# SysACE_SysFLASH.net
KiCad netlist of a schematic drawn in Altium Designer
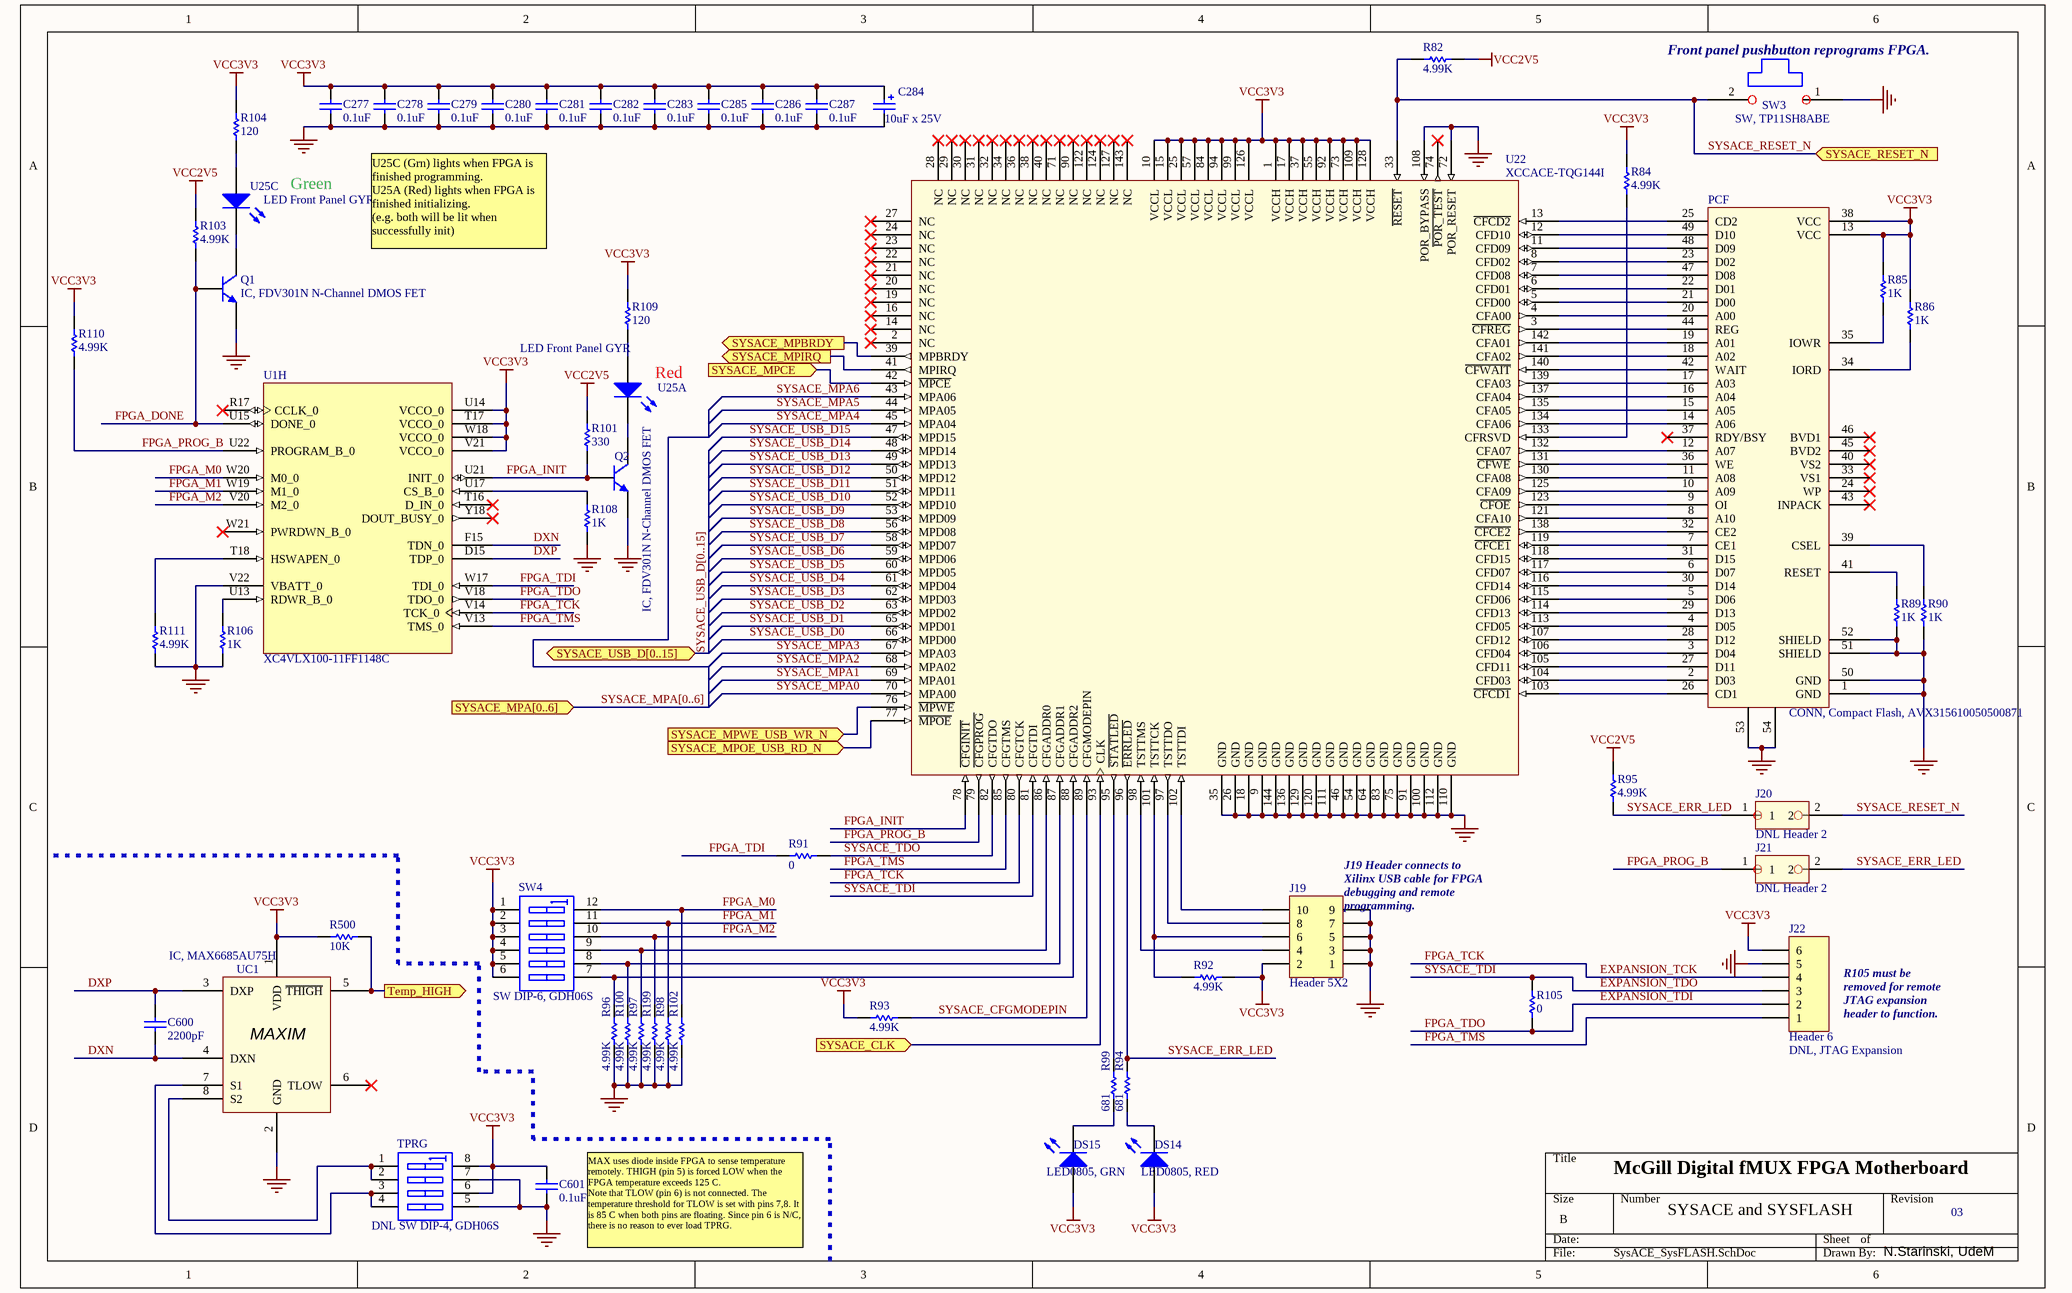
[diagram p0: SysACE_SysFLASH.SchDoc]

(export (version "E")
  (design (tool "Eeschema 10.0.6"))
  (components
    (comp (ref "C277")
      (value "0.1uF")
      (footprint "CC1608-0603")
      (description "Capacitor (Semiconductor SIM Model)")
      (fields (field (name "PUBLISHER") "Altium Limited"))
      (libsource (lib "Miscellaneous Devices") (part "Cap Semi"))
    )
    (comp (ref "C278")
      (value "0.1uF")
      (footprint "CC1608-0603")
      (description "Capacitor (Semiconductor SIM Model)")
      (fields (field (name "PUBLISHER") "Altium Limited"))
      (libsource (lib "Miscellaneous Devices") (part "Cap Semi"))
    )
    (comp (ref "C279")
      (value "0.1uF")
      (footprint "CC1608-0603")
      (description "Capacitor (Semiconductor SIM Model)")
      (fields (field (name "PUBLISHER") "Altium Limited"))
      (libsource (lib "Miscellaneous Devices") (part "Cap Semi"))
    )
    (comp (ref "C280")
      (value "0.1uF")
      (footprint "CC1608-0603")
      (description "Capacitor (Semiconductor SIM Model)")
      (fields (field (name "PUBLISHER") "Altium Limited"))
      (libsource (lib "Miscellaneous Devices") (part "Cap Semi"))
    )
    (comp (ref "C281")
      (value "0.1uF")
      (footprint "CC1608-0603")
      (description "Capacitor (Semiconductor SIM Model)")
      (fields (field (name "PUBLISHER") "Altium Limited"))
      (libsource (lib "Miscellaneous Devices") (part "Cap Semi"))
    )
    (comp (ref "C282")
      (value "0.1uF")
      (footprint "CC1608-0603")
      (description "Capacitor (Semiconductor SIM Model)")
      (fields (field (name "PUBLISHER") "Altium Limited"))
      (libsource (lib "Miscellaneous Devices") (part "Cap Semi"))
    )
    (comp (ref "C283")
      (value "0.1uF")
      (footprint "CC1608-0603")
      (description "Capacitor (Semiconductor SIM Model)")
      (fields (field (name "PUBLISHER") "Altium Limited"))
      (libsource (lib "Miscellaneous Devices") (part "Cap Semi"))
    )
    (comp (ref "C284")
      (value "10uF x 25V")
      (footprint "TC6032-2412")
      (description "CAP POL B45197A5106K309")
      (fields (field (name "PUBLISHER") "Altium Limited"))
      (libsource (lib "Miscellaneous Devices 02") (part "Cap Pol3"))
    )
    (comp (ref "C285")
      (value "0.1uF")
      (footprint "CC1608-0603")
      (description "Capacitor (Semiconductor SIM Model)")
      (fields (field (name "PUBLISHER") "Altium Limited"))
      (libsource (lib "Miscellaneous Devices") (part "Cap Semi"))
    )
    (comp (ref "C286")
      (value "0.1uF")
      (footprint "CC1608-0603")
      (description "Capacitor (Semiconductor SIM Model)")
      (fields (field (name "PUBLISHER") "Altium Limited"))
      (libsource (lib "Miscellaneous Devices") (part "Cap Semi"))
    )
    (comp (ref "C287")
      (value "0.1uF")
      (footprint "CC1608-0603")
      (description "Capacitor (Semiconductor SIM Model)")
      (fields (field (name "PUBLISHER") "Altium Limited"))
      (libsource (lib "Miscellaneous Devices") (part "Cap Semi"))
    )
    (comp (ref "C600")
      (value "2200pF")
      (footprint "CC1608-0603")
      (description "Capacitor (Semiconductor SIM Model)")
      (fields (field (name "PUBLISHER") "Altium Limited"))
      (libsource (lib "Miscellaneous Devices") (part "Cap Semi"))
    )
    (comp (ref "C601")
      (value "0.1uF")
      (footprint "CC1608-0603")
      (description "Capacitor (Semiconductor SIM Model)")
      (fields (field (name "PUBLISHER") "Altium Limited"))
      (libsource (lib "Miscellaneous Devices") (part "Cap Semi"))
    )
    (comp (ref "DS14")
      (value "LED0805, RED")
      (footprint "SMD _LED")
      (description "LED 0805 LTST-C170CKT")
      (fields (field (name "PUBLISHER") "Altium Limited"))
      (libsource (lib "Miscellaneous Devices") (part "LED3"))
    )
    (comp (ref "DS15")
      (value "LED0805, GRN")
      (footprint "SMD _LED")
      (description "LED 0805 LTST-C170GKT")
      (fields (field (name "PUBLISHER") "Altium Limited"))
      (libsource (lib "Miscellaneous Devices") (part "LED3"))
    )
    (comp (ref "J19")
      (value "Header 5X2")
      (footprint "HDR2X5")
      (description "Header, 0.1\" 5-Pin, Dual row straight")
      (fields (field (name "PUBLISHER") "Altium Limited"))
      (libsource (lib "Miscellaneous Connectors") (part "Header 5X2"))
    )
    (comp (ref "J20")
      (value "DNL Header 2")
      (footprint "HDR1X2")
      (description "Header, 0.1\" 2-Pin straight")
      (libsource (lib "MyComp1") (part "Jumper_100mil"))
    )
    (comp (ref "J21")
      (value "DNL Header 2")
      (footprint "HDR1X2")
      (description "Header, 0.1\" 2-Pin straight")
      (libsource (lib "MyComp1") (part "Jumper_100mil"))
    )
    (comp (ref "J22")
      (value "Header 6")
      (footprint "HDR1X6")
      (description "Header, 0.1\" 6-Pin straight")
      (fields (field (name "ASSEMBLY") "DNL, JTAG Expansion") (field (name "PUBLISHER") "Altium Limited"))
      (libsource (lib "Miscellaneous Connectors") (part "Header 6"))
    )
    (comp (ref "PCF")
      (value "CONN, Compact Flash, AVX315610050500871")
      (footprint "CF_AVX5611")
      (description "Compact Flash Connector")
      (libsource (lib "MyComp1") (part "CF_Conn"))
    )
    (comp (ref "Q1")
      (value "IC, FDV301N N-Channel DMOS FET")
      (footprint "Philips Discrete BJT - Low Power:SOT23")
      (description "NPN Switching Transistor")
      (fields (field (name "PUBLISHER") "Altium Limited"))
      (libsource (lib "Philips Discrete BJT - Low Power") (part "MMBT3904"))
    )
    (comp (ref "Q2")
      (value "IC, FDV301N N-Channel DMOS FET")
      (footprint "Philips Discrete BJT - Low Power:SOT23")
      (description "NPN Switching Transistor")
      (fields (field (name "PUBLISHER") "Altium Limited"))
      (libsource (lib "Philips Discrete BJT - Low Power") (part "MMBT3904"))
    )
    (comp (ref "R82")
      (value "4.99K")
      (footprint "CR1608-0603")
      (description "Resistor 0603")
      (fields (field (name "PUBLISHER") "Altium Limited"))
      (libsource (lib "Miscellaneous Devices") (part "Res Semi"))
    )
    (comp (ref "R84")
      (value "4.99K")
      (footprint "CR1608-0603")
      (description "Resistor 0603")
      (fields (field (name "PUBLISHER") "Altium Limited"))
      (libsource (lib "Miscellaneous Devices") (part "Res Semi"))
    )
    (comp (ref "R85")
      (value "1K")
      (footprint "CR1608-0603")
      (description "Resistor 0603")
      (fields (field (name "PUBLISHER") "Altium Limited"))
      (libsource (lib "Miscellaneous Devices") (part "Res Semi"))
    )
    (comp (ref "R86")
      (value "1K")
      (footprint "CR1608-0603")
      (description "Resistor 0603")
      (fields (field (name "PUBLISHER") "Altium Limited"))
      (libsource (lib "Miscellaneous Devices") (part "Res Semi"))
    )
    (comp (ref "R89")
      (value "1K")
      (footprint "CR1608-0603")
      (description "Resistor 0603")
      (fields (field (name "PUBLISHER") "Altium Limited"))
      (libsource (lib "Miscellaneous Devices") (part "Res Semi"))
    )
    (comp (ref "R90")
      (value "1K")
      (footprint "CR1608-0603")
      (description "Resistor 0603")
      (fields (field (name "PUBLISHER") "Altium Limited"))
      (libsource (lib "Miscellaneous Devices") (part "Res Semi"))
    )
    (comp (ref "R91")
      (value "0")
      (footprint "CR1608-0603")
      (description "Resistor 0603")
      (fields (field (name "PUBLISHER") "Altium Limited"))
      (libsource (lib "Miscellaneous Devices") (part "Res Semi"))
    )
    (comp (ref "R92")
      (value "4.99K")
      (footprint "CR1608-0603")
      (description "Resistor 0603")
      (fields (field (name "PUBLISHER") "Altium Limited"))
      (libsource (lib "Miscellaneous Devices") (part "Res Semi"))
    )
    (comp (ref "R93")
      (value "4.99K")
      (footprint "CR1608-0603")
      (description "Resistor 0603")
      (fields (field (name "PUBLISHER") "Altium Limited"))
      (libsource (lib "Miscellaneous Devices") (part "Res Semi"))
    )
    (comp (ref "R94")
      (value "681")
      (footprint "CR1608-0603")
      (description "Resistor 0603")
      (fields (field (name "PUBLISHER") "Altium Limited"))
      (libsource (lib "Miscellaneous Devices") (part "Res Semi"))
    )
    (comp (ref "R95")
      (value "4.99K")
      (footprint "CR1608-0603")
      (description "Resistor 0603")
      (fields (field (name "PUBLISHER") "Altium Limited"))
      (libsource (lib "Miscellaneous Devices") (part "Res Semi"))
    )
    (comp (ref "R96")
      (value "4.99K")
      (footprint "CR1608-0603")
      (description "Resistor 0603")
      (fields (field (name "PUBLISHER") "Altium Limited"))
      (libsource (lib "Miscellaneous Devices") (part "Res Semi"))
    )
    (comp (ref "R97")
      (value "4.99K")
      (footprint "CR1608-0603")
      (description "Resistor 0603")
      (fields (field (name "PUBLISHER") "Altium Limited"))
      (libsource (lib "Miscellaneous Devices") (part "Res Semi"))
    )
    (comp (ref "R98")
      (value "4.99K")
      (footprint "CR1608-0603")
      (description "Resistor 0603")
      (fields (field (name "PUBLISHER") "Altium Limited"))
      (libsource (lib "Miscellaneous Devices") (part "Res Semi"))
    )
    (comp (ref "R99")
      (value "681")
      (footprint "CR1608-0603")
      (description "Resistor 0603")
      (fields (field (name "PUBLISHER") "Altium Limited"))
      (libsource (lib "Miscellaneous Devices") (part "Res Semi"))
    )
    (comp (ref "R100")
      (value "4.99K")
      (footprint "CR1608-0603")
      (description "Resistor 0603")
      (fields (field (name "PUBLISHER") "Altium Limited"))
      (libsource (lib "Miscellaneous Devices") (part "Res Semi"))
    )
    (comp (ref "R101")
      (value "330")
      (footprint "CR1608-0603")
      (description "Resistor 0603")
      (fields (field (name "PUBLISHER") "Altium Limited"))
      (libsource (lib "Miscellaneous Devices") (part "Res Semi"))
    )
    (comp (ref "R102")
      (value "4.99K")
      (footprint "CR1608-0603")
      (description "Resistor 0603")
      (fields (field (name "PUBLISHER") "Altium Limited"))
      (libsource (lib "Miscellaneous Devices") (part "Res Semi"))
    )
    (comp (ref "R103")
      (value "4.99K")
      (footprint "CR1608-0603")
      (description "Resistor 0603")
      (fields (field (name "PUBLISHER") "Altium Limited"))
      (libsource (lib "Miscellaneous Devices") (part "Res Semi"))
    )
    (comp (ref "R104")
      (value "120")
      (footprint "CR1608-0603")
      (description "Resistor 0603")
      (fields (field (name "PUBLISHER") "Altium Limited"))
      (libsource (lib "Miscellaneous Devices") (part "Res Semi"))
    )
    (comp (ref "R105")
      (value "0")
      (footprint "CR1608-0603")
      (description "Resistor 0603")
      (fields (field (name "PUBLISHER") "Altium Limited"))
      (libsource (lib "Miscellaneous Devices") (part "Res Semi"))
    )
    (comp (ref "R106")
      (value "1K")
      (footprint "CR1608-0603")
      (description "Resistor 0603")
      (fields (field (name "PUBLISHER") "Altium Limited"))
      (libsource (lib "Miscellaneous Devices") (part "Res Semi"))
    )
    (comp (ref "R108")
      (value "1K")
      (footprint "CR1608-0603")
      (description "Resistor 0603")
      (fields (field (name "PUBLISHER") "Altium Limited"))
      (libsource (lib "Miscellaneous Devices") (part "Res Semi"))
    )
    (comp (ref "R109")
      (value "120")
      (footprint "CR1608-0603")
      (description "Resistor 0603")
      (fields (field (name "PUBLISHER") "Altium Limited"))
      (libsource (lib "Miscellaneous Devices") (part "Res Semi"))
    )
    (comp (ref "R110")
      (value "4.99K")
      (footprint "CR1608-0603")
      (description "Resistor 0603")
      (fields (field (name "PUBLISHER") "Altium Limited"))
      (libsource (lib "Miscellaneous Devices") (part "Res Semi"))
    )
    (comp (ref "R111")
      (value "4.99K")
      (footprint "CR1608-0603")
      (description "Resistor 0603")
      (fields (field (name "PUBLISHER") "Altium Limited"))
      (libsource (lib "Miscellaneous Devices") (part "Res Semi"))
    )
    (comp (ref "R199")
      (value "4.99K")
      (footprint "CR1608-0603")
      (description "Resistor 0603")
      (fields (field (name "PUBLISHER") "Altium Limited"))
      (libsource (lib "Miscellaneous Devices") (part "Res Semi"))
    )
    (comp (ref "R500")
      (value "10K")
      (footprint "CR1608-0603")
      (description "Resistor 0603")
      (fields (field (name "PUBLISHER") "Altium Limited"))
      (libsource (lib "Miscellaneous Devices") (part "Res Semi"))
    )
    (comp (ref "SW3")
      (value "SW, TP11SH8ABE")
      (footprint "TP11SH8ABE")
      (description "Right angle PC trough")
      (libsource (lib "Miscellaneous Devices 02") (part "Tiny Pushbutton Switch"))
    )
    (comp (ref "SW4")
      (value "SW DIP-6, GDH06S")
      (footprint "DIP_SW_SM6POS")
      (description "DIP Switch, 6 Position, SPST")
      (fields (field (name "PUBLISHER") "Altium Limited"))
      (libsource (lib "Miscellaneous Devices 02") (part "SW DIP-6"))
    )
    (comp (ref "TPRG")
      (value "DNL SW DIP-4, GDH06S")
      (footprint "SO-G8")
      (description "DIP Switch, 4 Position, SPST")
      (fields (field (name "PUBLISHER") "Altium Limited"))
      (libsource (lib "Miscellaneous Devices 02") (part "SW DIP-4"))
    )
    (comp (ref "U1")
      (value "XC4VLX100-11FF1148C")
      (footprint "FF1148")
      (description "Xilinx Virtex-4 LX Platform FPGA, 1148-Ball FFBGA, Speed Grade 11, 768 User I/Os, Commercial Grade")
      (fields (field (name "PUBLISHER") "Altium Limited"))
      (libsource (lib "Xilinx Virtex-4") (part "XC4VLX100-11FF1148C"))
    )
    (comp (ref "U22")
      (value "XCCACE-TQG144I")
      (footprint "TQFP144")
      (description "System ACE CF Xilinx")
      (libsource (lib "Xilinx_Extra_01") (part "XCCACE-TQG144I"))
    )
    (comp (ref "U25")
      (value "LED Front Panel GYR")
      (footprint "LED_Tri_")
      (description "564-0200-132F")
      (libsource (lib "Miscellaneous Devices") (part "LED_Tri"))
    )
    (comp (ref "UC1")
      (value "IC, MAX6685AU75H")
      (footprint "uSOP8")
      (description "Dual-Output Remote-Junction Temperature Switch")
      (libsource (lib "Maxim Power Mgt Supervisory Circuit") (part "MAX6685"))
    )
  )
  (nets
    (net (code "1") (name "/DXN") (class "Default")
      (node (ref "C600") (pin "1") (pinfunction "1_1") (pintype "passive"))
      (node (ref "U1") (pin "F15") (pinfunction "TDN_0_F15") (pintype "passive"))
      (node (ref "UC1") (pin "4") (pinfunction "DXN_4") (pintype "passive"))
    )
    (net (code "2") (name "/DXP") (class "Default")
      (node (ref "C600") (pin "2") (pinfunction "2_2") (pintype "passive"))
      (node (ref "U1") (pin "D15") (pinfunction "TDP_0_D15") (pintype "passive"))
      (node (ref "UC1") (pin "3") (pinfunction "DXP_3") (pintype "passive"))
    )
    (net (code "3") (name "/EXPANSION_TCK") (class "Default")
      (node (ref "J22") (pin "4") (pinfunction "4_4") (pintype "passive"))
      (node (ref "U1") (pin "V14") (pinfunction "TCK_0_V14") (pintype "input"))
      (node (ref "U22") (pin "80") (pinfunction "CFGTCK_80") (pintype "output"))
    )
    (net (code "4") (name "/EXPANSION_TDI") (class "Default")
      (node (ref "J22") (pin "2") (pinfunction "2_2") (pintype "passive"))
      (node (ref "R105") (pin "1") (pinfunction "1_1") (pintype "passive"))
      (node (ref "U1") (pin "V18") (pinfunction "TDO_0_V18") (pintype "output"))
    )
    (net (code "5") (name "/EXPANSION_TDO") (class "Default")
      (node (ref "J22") (pin "3") (pinfunction "3_3") (pintype "passive"))
      (node (ref "R105") (pin "2") (pinfunction "2_2") (pintype "passive"))
      (node (ref "U22") (pin "81") (pinfunction "CFGTDI_81") (pintype "input"))
    )
    (net (code "6") (name "/FPGA_DONE") (class "Default")
      (node (ref "Q1") (pin "1") (pinfunction "B_1") (pintype "passive"))
      (node (ref "R103") (pin "1") (pinfunction "1_1") (pintype "passive"))
      (node (ref "U1") (pin "U15") (pinfunction "DONE_0_U15") (pintype "bidirectional"))
    )
    (net (code "7") (name "/FPGA_INIT") (class "Default")
      (node (ref "Q2") (pin "1") (pinfunction "B_1") (pintype "passive"))
      (node (ref "R101") (pin "1") (pinfunction "1_1") (pintype "passive"))
      (node (ref "U1") (pin "U21") (pinfunction "INIT_0_U21") (pintype "bidirectional"))
      (node (ref "U22") (pin "78") (pinfunction "~{CFGINIT}_78") (pintype "input"))
    )
    (net (code "8") (name "/FPGA_M0") (class "Default")
      (node (ref "R102") (pin "2") (pinfunction "2_2") (pintype "passive"))
      (node (ref "SW4") (pin "12") (pinfunction "B1_12") (pintype "passive"))
      (node (ref "U1") (pin "W20") (pinfunction "M0_0_W20") (pintype "input"))
    )
    (net (code "9") (name "/FPGA_M1") (class "Default")
      (node (ref "R98") (pin "2") (pinfunction "2_2") (pintype "passive"))
      (node (ref "SW4") (pin "11") (pinfunction "B2_11") (pintype "passive"))
      (node (ref "U1") (pin "W19") (pinfunction "M1_0_W19") (pintype "input"))
    )
    (net (code "10") (name "/FPGA_M2") (class "Default")
      (node (ref "R199") (pin "2") (pinfunction "2_2") (pintype "passive"))
      (node (ref "SW4") (pin "10") (pinfunction "B3_10") (pintype "passive"))
      (node (ref "U1") (pin "V20") (pinfunction "M2_0_V20") (pintype "input"))
    )
    (net (code "11") (name "/FPGA_PROG_B") (class "Default")
      (node (ref "J21") (pin "1") (pinfunction "1_1") (pintype "passive"))
      (node (ref "R110") (pin "1") (pinfunction "1_1") (pintype "passive"))
      (node (ref "U1") (pin "U22") (pinfunction "PROGRAM_B_0_U22") (pintype "input"))
      (node (ref "U22") (pin "79") (pinfunction "~{CFGPROG}_79") (pintype "output"))
    )
    (net (code "12") (name "/FPGA_TDI") (class "Default")
      (node (ref "R91") (pin "1") (pinfunction "1_1") (pintype "passive"))
      (node (ref "U1") (pin "W17") (pinfunction "TDI_0_W17") (pintype "input"))
    )
    (net (code "13") (name "/FPGA_TMS") (class "Default")
      (node (ref "J22") (pin "1") (pinfunction "1_1") (pintype "passive"))
      (node (ref "U1") (pin "V13") (pinfunction "TMS_0_V13") (pintype "input"))
      (node (ref "U22") (pin "85") (pinfunction "CFGTMS_85") (pintype "output"))
    )
    (net (code "14") (name "/SYSACE_CFGMODEPIN") (class "Default")
      (node (ref "R93") (pin "2") (pinfunction "2_2") (pintype "passive"))
      (node (ref "U22") (pin "89") (pinfunction "CFGMODEPIN_89") (pintype "input"))
    )
    (net (code "15") (name "/SYSACE_CLK") (class "Default")
      (node (ref "U22") (pin "93") (pinfunction "CLK_93") (pintype "input"))
    )
    (net (code "16") (name "/SYSACE_ERR_LED") (class "Default")
      (node (ref "J20") (pin "1") (pinfunction "1_1") (pintype "passive"))
      (node (ref "J21") (pin "2") (pinfunction "2_2") (pintype "passive"))
      (node (ref "R94") (pin "2") (pinfunction "2_2") (pintype "passive"))
      (node (ref "R95") (pin "1") (pinfunction "1_1") (pintype "passive"))
      (node (ref "U22") (pin "96") (pinfunction "~{ERRLED}_96") (pintype "output"))
    )
    (net (code "17") (name "/SYSACE_MPA0") (class "Default")
      (node (ref "U22") (pin "70") (pinfunction "MPA00_70") (pintype "input"))
    )
    (net (code "18") (name "/SYSACE_MPA1") (class "Default")
      (node (ref "U22") (pin "69") (pinfunction "MPA01_69") (pintype "input"))
    )
    (net (code "19") (name "/SYSACE_MPA2") (class "Default")
      (node (ref "U22") (pin "68") (pinfunction "MPA02_68") (pintype "input"))
    )
    (net (code "20") (name "/SYSACE_MPA3") (class "Default")
      (node (ref "U22") (pin "67") (pinfunction "MPA03_67") (pintype "input"))
    )
    (net (code "21") (name "/SYSACE_MPA4") (class "Default")
      (node (ref "U22") (pin "45") (pinfunction "MPA04_45") (pintype "input"))
    )
    (net (code "22") (name "/SYSACE_MPA5") (class "Default")
      (node (ref "U22") (pin "44") (pinfunction "MPA05_44") (pintype "input"))
    )
    (net (code "23") (name "/SYSACE_MPA6") (class "Default")
      (node (ref "U22") (pin "43") (pinfunction "MPA06_43") (pintype "input"))
    )
    (net (code "25") (name "/SYSACE_MPBRDY") (class "Default")
      (node (ref "U22") (pin "39") (pinfunction "MPBRDY_39") (pintype "output"))
    )
    (net (code "26") (name "/SYSACE_MPCE") (class "Default")
      (node (ref "U22") (pin "42") (pinfunction "~{MPCE}_42") (pintype "input"))
    )
    (net (code "27") (name "/SYSACE_MPIRQ") (class "Default")
      (node (ref "U22") (pin "41") (pinfunction "MPIRQ_41") (pintype "output"))
    )
    (net (code "28") (name "/SYSACE_MPOE_USB_RD_N") (class "Default")
      (node (ref "U22") (pin "77") (pinfunction "~{MPOE}_77") (pintype "input"))
    )
    (net (code "29") (name "/SYSACE_MPWE_USB_WR_N") (class "Default")
      (node (ref "U22") (pin "76") (pinfunction "~{MPWE}_76") (pintype "input"))
    )
    (net (code "30") (name "/SYSACE_RESET_N") (class "Default")
      (node (ref "J20") (pin "2") (pinfunction "2_2") (pintype "passive"))
      (node (ref "R82") (pin "1") (pinfunction "1_1") (pintype "passive"))
      (node (ref "SW3") (pin "2") (pinfunction "2_2") (pintype "passive"))
      (node (ref "U22") (pin "33") (pinfunction "~{RESET}_33") (pintype "input"))
    )
    (net (code "31") (name "/SYSACE_TDO") (class "Default")
      (node (ref "R91") (pin "2") (pinfunction "2_2") (pintype "passive"))
      (node (ref "U22") (pin "82") (pinfunction "CFGTDO_82") (pintype "output"))
    )
    (net (code "32") (name "/SYSACE_USB_D0") (class "Default")
      (node (ref "U22") (pin "66") (pinfunction "MPD00_66") (pintype "bidirectional"))
    )
    (net (code "33") (name "/SYSACE_USB_D1") (class "Default")
      (node (ref "U22") (pin "65") (pinfunction "MPD01_65") (pintype "bidirectional"))
    )
    (net (code "34") (name "/SYSACE_USB_D2") (class "Default")
      (node (ref "U22") (pin "63") (pinfunction "MPD02_63") (pintype "bidirectional"))
    )
    (net (code "35") (name "/SYSACE_USB_D3") (class "Default")
      (node (ref "U22") (pin "62") (pinfunction "MPD03_62") (pintype "bidirectional"))
    )
    (net (code "36") (name "/SYSACE_USB_D4") (class "Default")
      (node (ref "U22") (pin "61") (pinfunction "MPD04_61") (pintype "bidirectional"))
    )
    (net (code "37") (name "/SYSACE_USB_D5") (class "Default")
      (node (ref "U22") (pin "60") (pinfunction "MPD05_60") (pintype "bidirectional"))
    )
    (net (code "38") (name "/SYSACE_USB_D6") (class "Default")
      (node (ref "U22") (pin "59") (pinfunction "MPD06_59") (pintype "bidirectional"))
    )
    (net (code "39") (name "/SYSACE_USB_D7") (class "Default")
      (node (ref "U22") (pin "58") (pinfunction "MPD07_58") (pintype "bidirectional"))
    )
    (net (code "40") (name "/SYSACE_USB_D8") (class "Default")
      (node (ref "U22") (pin "56") (pinfunction "MPD08_56") (pintype "bidirectional"))
    )
    (net (code "41") (name "/SYSACE_USB_D9") (class "Default")
      (node (ref "U22") (pin "53") (pinfunction "MPD09_53") (pintype "bidirectional"))
    )
    (net (code "42") (name "/SYSACE_USB_D10") (class "Default")
      (node (ref "U22") (pin "52") (pinfunction "MPD10_52") (pintype "bidirectional"))
    )
    (net (code "43") (name "/SYSACE_USB_D11") (class "Default")
      (node (ref "U22") (pin "51") (pinfunction "MPD11_51") (pintype "bidirectional"))
    )
    (net (code "44") (name "/SYSACE_USB_D12") (class "Default")
      (node (ref "U22") (pin "50") (pinfunction "MPD12_50") (pintype "bidirectional"))
    )
    (net (code "45") (name "/SYSACE_USB_D13") (class "Default")
      (node (ref "U22") (pin "49") (pinfunction "MPD13_49") (pintype "bidirectional"))
    )
    (net (code "46") (name "/SYSACE_USB_D14") (class "Default")
      (node (ref "U22") (pin "48") (pinfunction "MPD14_48") (pintype "bidirectional"))
    )
    (net (code "47") (name "/SYSACE_USB_D15") (class "Default")
      (node (ref "U22") (pin "47") (pinfunction "MPD15_47") (pintype "bidirectional"))
    )
    (net (code "49") (name "/Temp_HIGH") (class "Default")
      (node (ref "R500") (pin "2") (pinfunction "2_2") (pintype "passive"))
      (node (ref "UC1") (pin "5") (pinfunction "~{THIGH}_5") (pintype "passive"))
    )
    (net (code "50") (name "GND") (class "Default")
      (node (ref "C277") (pin "1") (pinfunction "1_1") (pintype "passive"))
      (node (ref "C278") (pin "1") (pinfunction "1_1") (pintype "passive"))
      (node (ref "C279") (pin "1") (pinfunction "1_1") (pintype "passive"))
      (node (ref "C280") (pin "1") (pinfunction "1_1") (pintype "passive"))
      (node (ref "C281") (pin "1") (pinfunction "1_1") (pintype "passive"))
      (node (ref "C282") (pin "1") (pinfunction "1_1") (pintype "passive"))
      (node (ref "C283") (pin "1") (pinfunction "1_1") (pintype "passive"))
      (node (ref "C284") (pin "2") (pinfunction "2_2") (pintype "passive"))
      (node (ref "C285") (pin "1") (pinfunction "1_1") (pintype "passive"))
      (node (ref "C286") (pin "1") (pinfunction "1_1") (pintype "passive"))
      (node (ref "C287") (pin "1") (pinfunction "1_1") (pintype "passive"))
      (node (ref "C601") (pin "1") (pinfunction "1_1") (pintype "passive"))
      (node (ref "J19") (pin "1") (pinfunction "1_1") (pintype "passive"))
      (node (ref "J19") (pin "3") (pinfunction "3_3") (pintype "passive"))
      (node (ref "J19") (pin "5") (pinfunction "5_5") (pintype "passive"))
      (node (ref "J19") (pin "7") (pinfunction "7_7") (pintype "passive"))
      (node (ref "J19") (pin "9") (pinfunction "9_9") (pintype "passive"))
      (node (ref "J22") (pin "5") (pinfunction "5_5") (pintype "passive"))
      (node (ref "PCF") (pin "1") (pinfunction "GND_1") (pintype "passive"))
      (node (ref "PCF") (pin "50") (pinfunction "GND_50") (pintype "passive"))
      (node (ref "PCF") (pin "51") (pinfunction "SHIELD_51") (pintype "passive"))
      (node (ref "PCF") (pin "52") (pinfunction "SHIELD_52") (pintype "passive"))
      (node (ref "PCF") (pin "53") (pinfunction "GND_53") (pintype "passive"))
      (node (ref "PCF") (pin "54") (pinfunction "GND_54") (pintype "passive"))
      (node (ref "Q1") (pin "2") (pinfunction "E_2") (pintype "passive"))
      (node (ref "Q2") (pin "2") (pinfunction "E_2") (pintype "passive"))
      (node (ref "R100") (pin "1") (pinfunction "1_1") (pintype "passive"))
      (node (ref "R102") (pin "1") (pinfunction "1_1") (pintype "passive"))
      (node (ref "R106") (pin "1") (pinfunction "1_1") (pintype "passive"))
      (node (ref "R108") (pin "1") (pinfunction "1_1") (pintype "passive"))
      (node (ref "R111") (pin "1") (pinfunction "1_1") (pintype "passive"))
      (node (ref "R199") (pin "1") (pinfunction "1_1") (pintype "passive"))
      (node (ref "R89") (pin "1") (pinfunction "1_1") (pintype "passive"))
      (node (ref "R90") (pin "1") (pinfunction "1_1") (pintype "passive"))
      (node (ref "R96") (pin "1") (pinfunction "1_1") (pintype "passive"))
      (node (ref "R97") (pin "1") (pinfunction "1_1") (pintype "passive"))
      (node (ref "R98") (pin "1") (pinfunction "1_1") (pintype "passive"))
      (node (ref "SW3") (pin "1") (pinfunction "1_1") (pintype "passive"))
      (node (ref "TPRG") (pin "5") (pinfunction "B4_5") (pintype "passive"))
      (node (ref "TPRG") (pin "7") (pinfunction "B2_7") (pintype "passive"))
      (node (ref "U1") (pin "V22") (pinfunction "VBATT_0_V22") (pintype "power_in"))
      (node (ref "U22") (pin "100") (pinfunction "GND_100") (pintype "power_in"))
      (node (ref "U22") (pin "108") (pinfunction "POR_BYPASS_108") (pintype "input"))
      (node (ref "U22") (pin "110") (pinfunction "GND_110") (pintype "power_in"))
      (node (ref "U22") (pin "111") (pinfunction "GND_111") (pintype "power_in"))
      (node (ref "U22") (pin "112") (pinfunction "GND_112") (pintype "power_in"))
      (node (ref "U22") (pin "120") (pinfunction "GND_120") (pintype "power_in"))
      (node (ref "U22") (pin "129") (pinfunction "GND_129") (pintype "power_in"))
      (node (ref "U22") (pin "136") (pinfunction "GND_136") (pintype "power_in"))
      (node (ref "U22") (pin "144") (pinfunction "GND_144") (pintype "power_in"))
      (node (ref "U22") (pin "18") (pinfunction "GND_18") (pintype "power_in"))
      (node (ref "U22") (pin "26") (pinfunction "GND_26") (pintype "power_in"))
      (node (ref "U22") (pin "35") (pinfunction "GND_35") (pintype "power_in"))
      (node (ref "U22") (pin "46") (pinfunction "GND_46") (pintype "power_in"))
      (node (ref "U22") (pin "54") (pinfunction "GND_54") (pintype "power_in"))
      (node (ref "U22") (pin "64") (pinfunction "GND_64") (pintype "power_in"))
      (node (ref "U22") (pin "72") (pinfunction "POR_RESET_72") (pintype "input"))
      (node (ref "U22") (pin "75") (pinfunction "GND_75") (pintype "power_in"))
      (node (ref "U22") (pin "83") (pinfunction "GND_83") (pintype "power_in"))
      (node (ref "U22") (pin "9") (pinfunction "GND_9") (pintype "power_in"))
      (node (ref "U22") (pin "91") (pinfunction "GND_91") (pintype "power_in"))
      (node (ref "UC1") (pin "2") (pinfunction "GND_2") (pintype "power_in"))
    )
    (net (code "51") (name "Net-(DS14-K)") (class "Default")
      (node (ref "DS14") (pin "2") (pinfunction "K_2") (pintype "passive"))
      (node (ref "R94") (pin "1") (pinfunction "1_1") (pintype "passive"))
    )
    (net (code "52") (name "Net-(DS15-K)") (class "Default")
      (node (ref "DS15") (pin "2") (pinfunction "K_2") (pintype "passive"))
      (node (ref "R99") (pin "1") (pinfunction "1_1") (pintype "passive"))
    )
    (net (code "53") (name "Net-(PCF-A00)") (class "Default")
      (node (ref "PCF") (pin "20") (pinfunction "A00_20") (pintype "passive"))
      (node (ref "U22") (pin "4") (pinfunction "CFA00_4") (pintype "output"))
    )
    (net (code "54") (name "Net-(PCF-A01)") (class "Default")
      (node (ref "PCF") (pin "19") (pinfunction "A01_19") (pintype "passive"))
      (node (ref "U22") (pin "142") (pinfunction "CFA01_142") (pintype "output"))
    )
    (net (code "55") (name "Net-(PCF-A02)") (class "Default")
      (node (ref "PCF") (pin "18") (pinfunction "A02_18") (pintype "passive"))
      (node (ref "U22") (pin "141") (pinfunction "CFA02_141") (pintype "output"))
    )
    (net (code "56") (name "Net-(PCF-A03)") (class "Default")
      (node (ref "PCF") (pin "17") (pinfunction "A03_17") (pintype "passive"))
      (node (ref "U22") (pin "139") (pinfunction "CFA03_139") (pintype "output"))
    )
    (net (code "57") (name "Net-(PCF-A04)") (class "Default")
      (node (ref "PCF") (pin "16") (pinfunction "A04_16") (pintype "passive"))
      (node (ref "U22") (pin "137") (pinfunction "CFA04_137") (pintype "output"))
    )
    (net (code "58") (name "Net-(PCF-A05)") (class "Default")
      (node (ref "PCF") (pin "15") (pinfunction "A05_15") (pintype "passive"))
      (node (ref "U22") (pin "135") (pinfunction "CFA05_135") (pintype "output"))
    )
    (net (code "59") (name "Net-(PCF-A06)") (class "Default")
      (node (ref "PCF") (pin "14") (pinfunction "A06_14") (pintype "passive"))
      (node (ref "U22") (pin "134") (pinfunction "CFA06_134") (pintype "output"))
    )
    (net (code "60") (name "Net-(PCF-A07)") (class "Default")
      (node (ref "PCF") (pin "12") (pinfunction "A07_12") (pintype "passive"))
      (node (ref "U22") (pin "132") (pinfunction "CFA07_132") (pintype "output"))
    )
    (net (code "61") (name "Net-(PCF-A08)") (class "Default")
      (node (ref "PCF") (pin "11") (pinfunction "A08_11") (pintype "passive"))
      (node (ref "U22") (pin "130") (pinfunction "CFA08_130") (pintype "output"))
    )
    (net (code "62") (name "Net-(PCF-A09)") (class "Default")
      (node (ref "PCF") (pin "10") (pinfunction "A09_10") (pintype "passive"))
      (node (ref "U22") (pin "125") (pinfunction "CFA09_125") (pintype "output"))
    )
    (net (code "63") (name "Net-(PCF-A10)") (class "Default")
      (node (ref "PCF") (pin "8") (pinfunction "A10_8") (pintype "passive"))
      (node (ref "U22") (pin "121") (pinfunction "CFA10_121") (pintype "output"))
    )
    (net (code "64") (name "Net-(PCF-CD1)") (class "Default")
      (node (ref "PCF") (pin "26") (pinfunction "CD1_26") (pintype "passive"))
      (node (ref "U22") (pin "103") (pinfunction "~{CFCD1}_103") (pintype "input"))
    )
    (net (code "65") (name "Net-(PCF-CD2)") (class "Default")
      (node (ref "PCF") (pin "25") (pinfunction "CD2_25") (pintype "passive"))
      (node (ref "U22") (pin "13") (pinfunction "~{CFCD2}_13") (pintype "input"))
    )
    (net (code "66") (name "Net-(PCF-CE1)") (class "Default")
      (node (ref "PCF") (pin "7") (pinfunction "CE1_7") (pintype "passive"))
      (node (ref "U22") (pin "119") (pinfunction "~{CFCE1}_119") (pintype "bidirectional"))
    )
    (net (code "67") (name "Net-(PCF-CE2)") (class "Default")
      (node (ref "PCF") (pin "32") (pinfunction "CE2_32") (pintype "passive"))
      (node (ref "U22") (pin "138") (pinfunction "~{CFCE2}_138") (pintype "output"))
    )
    (net (code "68") (name "Net-(PCF-CSEL)") (class "Default")
      (node (ref "PCF") (pin "39") (pinfunction "CSEL_39") (pintype "passive"))
      (node (ref "R90") (pin "2") (pinfunction "2_2") (pintype "passive"))
    )
    (net (code "69") (name "Net-(PCF-D00)") (class "Default")
      (node (ref "PCF") (pin "21") (pinfunction "D00_21") (pintype "passive"))
      (node (ref "U22") (pin "5") (pinfunction "CFD00_5") (pintype "bidirectional"))
    )
    (net (code "70") (name "Net-(PCF-D01)") (class "Default")
      (node (ref "PCF") (pin "22") (pinfunction "D01_22") (pintype "passive"))
      (node (ref "U22") (pin "6") (pinfunction "CFD01_6") (pintype "bidirectional"))
    )
    (net (code "71") (name "Net-(PCF-D02)") (class "Default")
      (node (ref "PCF") (pin "23") (pinfunction "D02_23") (pintype "passive"))
      (node (ref "U22") (pin "8") (pinfunction "CFD02_8") (pintype "bidirectional"))
    )
    (net (code "72") (name "Net-(PCF-D03)") (class "Default")
      (node (ref "PCF") (pin "2") (pinfunction "D03_2") (pintype "passive"))
      (node (ref "U22") (pin "104") (pinfunction "CFD03_104") (pintype "bidirectional"))
    )
    (net (code "73") (name "Net-(PCF-D04)") (class "Default")
      (node (ref "PCF") (pin "3") (pinfunction "D04_3") (pintype "passive"))
      (node (ref "U22") (pin "106") (pinfunction "CFD04_106") (pintype "bidirectional"))
    )
    (net (code "74") (name "Net-(PCF-D05)") (class "Default")
      (node (ref "PCF") (pin "4") (pinfunction "D05_4") (pintype "passive"))
      (node (ref "U22") (pin "113") (pinfunction "CFD05_113") (pintype "bidirectional"))
    )
    (net (code "75") (name "Net-(PCF-D06)") (class "Default")
      (node (ref "PCF") (pin "5") (pinfunction "D06_5") (pintype "passive"))
      (node (ref "U22") (pin "115") (pinfunction "CFD06_115") (pintype "bidirectional"))
    )
    (net (code "76") (name "Net-(PCF-D07)") (class "Default")
      (node (ref "PCF") (pin "6") (pinfunction "D07_6") (pintype "passive"))
      (node (ref "U22") (pin "117") (pinfunction "CFD07_117") (pintype "bidirectional"))
    )
    (net (code "77") (name "Net-(PCF-D08)") (class "Default")
      (node (ref "PCF") (pin "47") (pinfunction "D08_47") (pintype "passive"))
      (node (ref "U22") (pin "7") (pinfunction "CFD08_7") (pintype "bidirectional"))
    )
    (net (code "78") (name "Net-(PCF-D09)") (class "Default")
      (node (ref "PCF") (pin "48") (pinfunction "D09_48") (pintype "passive"))
      (node (ref "U22") (pin "11") (pinfunction "CFD09_11") (pintype "bidirectional"))
    )
    (net (code "79") (name "Net-(PCF-D10)") (class "Default")
      (node (ref "PCF") (pin "49") (pinfunction "D10_49") (pintype "passive"))
      (node (ref "U22") (pin "12") (pinfunction "CFD10_12") (pintype "bidirectional"))
    )
    (net (code "80") (name "Net-(PCF-D11)") (class "Default")
      (node (ref "PCF") (pin "27") (pinfunction "D11_27") (pintype "passive"))
      (node (ref "U22") (pin "105") (pinfunction "CFD11_105") (pintype "bidirectional"))
    )
    (net (code "81") (name "Net-(PCF-D12)") (class "Default")
      (node (ref "PCF") (pin "28") (pinfunction "D12_28") (pintype "passive"))
      (node (ref "U22") (pin "107") (pinfunction "CFD12_107") (pintype "bidirectional"))
    )
    (net (code "82") (name "Net-(PCF-D13)") (class "Default")
      (node (ref "PCF") (pin "29") (pinfunction "D13_29") (pintype "passive"))
      (node (ref "U22") (pin "114") (pinfunction "CFD13_114") (pintype "bidirectional"))
    )
    (net (code "83") (name "Net-(PCF-D14)") (class "Default")
      (node (ref "PCF") (pin "30") (pinfunction "D14_30") (pintype "passive"))
      (node (ref "U22") (pin "116") (pinfunction "CFD14_116") (pintype "bidirectional"))
    )
    (net (code "84") (name "Net-(PCF-D15)") (class "Default")
      (node (ref "PCF") (pin "31") (pinfunction "D15_31") (pintype "passive"))
      (node (ref "U22") (pin "118") (pinfunction "CFD15_118") (pintype "bidirectional"))
    )
    (net (code "85") (name "Net-(PCF-IORD)") (class "Default")
      (node (ref "PCF") (pin "34") (pinfunction "IORD_34") (pintype "passive"))
      (node (ref "R86") (pin "1") (pinfunction "1_1") (pintype "passive"))
    )
    (net (code "86") (name "Net-(PCF-IOWR)") (class "Default")
      (node (ref "PCF") (pin "35") (pinfunction "IOWR_35") (pintype "passive"))
      (node (ref "R85") (pin "1") (pinfunction "1_1") (pintype "passive"))
    )
    (net (code "87") (name "Net-(PCF-OI)") (class "Default")
      (node (ref "PCF") (pin "9") (pinfunction "OI_9") (pintype "passive"))
      (node (ref "U22") (pin "123") (pinfunction "~{CFOE}_123") (pintype "output"))
    )
    (net (code "88") (name "Net-(PCF-REG)") (class "Default")
      (node (ref "PCF") (pin "44") (pinfunction "REG_44") (pintype "passive"))
      (node (ref "U22") (pin "3") (pinfunction "~{CFREG}_3") (pintype "output"))
    )
    (net (code "89") (name "Net-(PCF-RESET)") (class "Default")
      (node (ref "PCF") (pin "41") (pinfunction "RESET_41") (pintype "passive"))
      (node (ref "R89") (pin "2") (pinfunction "2_2") (pintype "passive"))
    )
    (net (code "90") (name "Net-(PCF-WAIT)") (class "Default")
      (node (ref "PCF") (pin "42") (pinfunction "WAIT_42") (pintype "passive"))
      (node (ref "U22") (pin "140") (pinfunction "~{CFWAIT}_140") (pintype "input"))
    )
    (net (code "91") (name "Net-(PCF-WE)") (class "Default")
      (node (ref "PCF") (pin "36") (pinfunction "WE_36") (pintype "passive"))
      (node (ref "U22") (pin "131") (pinfunction "~{CFWE}_131") (pintype "output"))
    )
    (net (code "92") (name "Net-(Q1-C)") (class "Default")
      (node (ref "Q1") (pin "3") (pinfunction "C_3") (pintype "passive"))
      (node (ref "U25") (pin "K3") (pinfunction "K_K3") (pintype "passive"))
    )
    (net (code "93") (name "Net-(Q2-C)") (class "Default")
      (node (ref "Q2") (pin "3") (pinfunction "C_3") (pintype "passive"))
      (node (ref "U25") (pin "K1") (pinfunction "K_K1") (pintype "passive"))
    )
    (net (code "94") (name "Net-(SW4-B4)") (class "Default")
      (node (ref "R97") (pin "2") (pinfunction "2_2") (pintype "passive"))
      (node (ref "SW4") (pin "9") (pinfunction "B4_9") (pintype "passive"))
      (node (ref "U22") (pin "86") (pinfunction "CFGADDR0_86") (pintype "input"))
    )
    (net (code "95") (name "Net-(SW4-B5)") (class "Default")
      (node (ref "R100") (pin "2") (pinfunction "2_2") (pintype "passive"))
      (node (ref "SW4") (pin "8") (pinfunction "B5_8") (pintype "passive"))
      (node (ref "U22") (pin "87") (pinfunction "CFGADDR1_87") (pintype "input"))
    )
    (net (code "96") (name "Net-(SW4-B6)") (class "Default")
      (node (ref "R96") (pin "2") (pinfunction "2_2") (pintype "passive"))
      (node (ref "SW4") (pin "7") (pinfunction "B6_7") (pintype "passive"))
      (node (ref "U22") (pin "88") (pinfunction "CFGADDR2_88") (pintype "input"))
    )
    (net (code "97") (name "Net-(TPRG-A1)") (class "Default")
      (node (ref "TPRG") (pin "1") (pinfunction "A1_1") (pintype "passive"))
      (node (ref "TPRG") (pin "2") (pinfunction "A2_2") (pintype "passive"))
      (node (ref "UC1") (pin "8") (pinfunction "S2_8") (pintype "passive"))
    )
    (net (code "98") (name "Net-(TPRG-A3)") (class "Default")
      (node (ref "TPRG") (pin "3") (pinfunction "A3_3") (pintype "passive"))
      (node (ref "TPRG") (pin "4") (pinfunction "A4_4") (pintype "passive"))
      (node (ref "UC1") (pin "7") (pinfunction "S1_7") (pintype "passive"))
    )
    (net (code "99") (name "Net-(U1H-CS_B_0)") (class "Default")
      (node (ref "R108") (pin "2") (pinfunction "2_2") (pintype "passive"))
      (node (ref "U1") (pin "U17") (pinfunction "CS_B_0_U17") (pintype "input"))
    )
    (net (code "100") (name "Net-(U1H-HSWAPEN_0)") (class "Default")
      (node (ref "R111") (pin "2") (pinfunction "2_2") (pintype "passive"))
      (node (ref "U1") (pin "T18") (pinfunction "HSWAPEN_0_T18") (pintype "input"))
    )
    (net (code "101") (name "Net-(U1H-RDWR_B_0)") (class "Default")
      (node (ref "R106") (pin "2") (pinfunction "2_2") (pintype "passive"))
      (node (ref "U1") (pin "U13") (pinfunction "RDWR_B_0_U13") (pintype "input"))
    )
    (net (code "102") (name "Net-(U22-CFRSVD)") (class "Default")
      (node (ref "R84") (pin "1") (pinfunction "1_1") (pintype "passive"))
      (node (ref "U22") (pin "133") (pinfunction "CFRSVD_133") (pintype "input"))
    )
    (net (code "103") (name "Net-(U22-TSTTCK)") (class "Default")
      (node (ref "J19") (pin "6") (pinfunction "6_6") (pintype "passive"))
      (node (ref "R92") (pin "1") (pinfunction "1_1") (pintype "passive"))
      (node (ref "U22") (pin "101") (pinfunction "TSTTCK_101") (pintype "input"))
    )
    (net (code "104") (name "Net-(U22-TSTTDI)") (class "Default")
      (node (ref "J19") (pin "10") (pinfunction "10_10") (pintype "passive"))
      (node (ref "U22") (pin "102") (pinfunction "TSTTDI_102") (pintype "input"))
    )
    (net (code "105") (name "Net-(U22-TSTTDO)") (class "Default")
      (node (ref "J19") (pin "8") (pinfunction "8_8") (pintype "passive"))
      (node (ref "U22") (pin "97") (pinfunction "TSTTDO_97") (pintype "output"))
    )
    (net (code "106") (name "Net-(U22-TSTTMS)") (class "Default")
      (node (ref "J19") (pin "4") (pinfunction "4_4") (pintype "passive"))
      (node (ref "U22") (pin "98") (pinfunction "TSTTMS_98") (pintype "input"))
    )
    (net (code "107") (name "Net-(U22-~{STATLED})") (class "Default")
      (node (ref "R99") (pin "2") (pinfunction "2_2") (pintype "passive"))
      (node (ref "U22") (pin "95") (pinfunction "~{STATLED}_95") (pintype "output"))
    )
    (net (code "108") (name "Net-(U25A-A)") (class "Default")
      (node (ref "R109") (pin "1") (pinfunction "1_1") (pintype "passive"))
      (node (ref "U25") (pin "A1") (pinfunction "A_A1") (pintype "passive"))
    )
    (net (code "109") (name "Net-(U25C-A)") (class "Default")
      (node (ref "R104") (pin "1") (pinfunction "1_1") (pintype "passive"))
      (node (ref "U25") (pin "A3") (pinfunction "A_A3") (pintype "passive"))
    )
    (net (code "110") (name "VCC2V5") (class "Default")
      (node (ref "R101") (pin "2") (pinfunction "2_2") (pintype "passive"))
      (node (ref "R103") (pin "2") (pinfunction "2_2") (pintype "passive"))
      (node (ref "R82") (pin "2") (pinfunction "2_2") (pintype "passive"))
      (node (ref "R95") (pin "2") (pinfunction "2_2") (pintype "passive"))
    )
    (net (code "111") (name "VCC3V3") (class "Default")
      (node (ref "C277") (pin "2") (pinfunction "2_2") (pintype "passive"))
      (node (ref "C278") (pin "2") (pinfunction "2_2") (pintype "passive"))
      (node (ref "C279") (pin "2") (pinfunction "2_2") (pintype "passive"))
      (node (ref "C280") (pin "2") (pinfunction "2_2") (pintype "passive"))
      (node (ref "C281") (pin "2") (pinfunction "2_2") (pintype "passive"))
      (node (ref "C282") (pin "2") (pinfunction "2_2") (pintype "passive"))
      (node (ref "C283") (pin "2") (pinfunction "2_2") (pintype "passive"))
      (node (ref "C284") (pin "1") (pinfunction "1_1") (pintype "passive"))
      (node (ref "C285") (pin "2") (pinfunction "2_2") (pintype "passive"))
      (node (ref "C286") (pin "2") (pinfunction "2_2") (pintype "passive"))
      (node (ref "C287") (pin "2") (pinfunction "2_2") (pintype "passive"))
      (node (ref "C601") (pin "2") (pinfunction "2_2") (pintype "passive"))
      (node (ref "DS14") (pin "1") (pinfunction "A_1") (pintype "passive"))
      (node (ref "DS15") (pin "1") (pinfunction "A_1") (pintype "passive"))
      (node (ref "J19") (pin "2") (pinfunction "2_2") (pintype "passive"))
      (node (ref "J22") (pin "6") (pinfunction "6_6") (pintype "passive"))
      (node (ref "PCF") (pin "13") (pinfunction "VCC_13") (pintype "passive"))
      (node (ref "PCF") (pin "38") (pinfunction "VCC_38") (pintype "passive"))
      (node (ref "R104") (pin "2") (pinfunction "2_2") (pintype "passive"))
      (node (ref "R109") (pin "2") (pinfunction "2_2") (pintype "passive"))
      (node (ref "R110") (pin "2") (pinfunction "2_2") (pintype "passive"))
      (node (ref "R500") (pin "1") (pinfunction "1_1") (pintype "passive"))
      (node (ref "R84") (pin "2") (pinfunction "2_2") (pintype "passive"))
      (node (ref "R85") (pin "2") (pinfunction "2_2") (pintype "passive"))
      (node (ref "R86") (pin "2") (pinfunction "2_2") (pintype "passive"))
      (node (ref "R92") (pin "2") (pinfunction "2_2") (pintype "passive"))
      (node (ref "R93") (pin "1") (pinfunction "1_1") (pintype "passive"))
      (node (ref "SW4") (pin "1") (pinfunction "A1_1") (pintype "passive"))
      (node (ref "SW4") (pin "2") (pinfunction "A2_2") (pintype "passive"))
      (node (ref "SW4") (pin "3") (pinfunction "A3_3") (pintype "passive"))
      (node (ref "SW4") (pin "4") (pinfunction "A4_4") (pintype "passive"))
      (node (ref "SW4") (pin "5") (pinfunction "A5_5") (pintype "passive"))
      (node (ref "SW4") (pin "6") (pinfunction "A6_6") (pintype "passive"))
      (node (ref "TPRG") (pin "6") (pinfunction "B3_6") (pintype "passive"))
      (node (ref "TPRG") (pin "8") (pinfunction "B1_8") (pintype "passive"))
      (node (ref "U1") (pin "T17") (pinfunction "VCCO_0_T17") (pintype "power_in"))
      (node (ref "U1") (pin "U14") (pinfunction "VCCO_0_U14") (pintype "power_in"))
      (node (ref "U1") (pin "V21") (pinfunction "VCCO_0_V21") (pintype "power_in"))
      (node (ref "U1") (pin "W18") (pinfunction "VCCO_0_W18") (pintype "power_in"))
      (node (ref "U22") (pin "1") (pinfunction "VCCH_1") (pintype "power_in"))
      (node (ref "U22") (pin "10") (pinfunction "VCCL_10") (pintype "power_in"))
      (node (ref "U22") (pin "109") (pinfunction "VCCH_109") (pintype "power_in"))
      (node (ref "U22") (pin "126") (pinfunction "VCCL_126") (pintype "power_in"))
      (node (ref "U22") (pin "128") (pinfunction "VCCH_128") (pintype "power_in"))
      (node (ref "U22") (pin "15") (pinfunction "VCCL_15") (pintype "power_in"))
      (node (ref "U22") (pin "17") (pinfunction "VCCH_17") (pintype "power_in"))
      (node (ref "U22") (pin "25") (pinfunction "VCCL_25") (pintype "power_in"))
      (node (ref "U22") (pin "37") (pinfunction "VCCH_37") (pintype "power_in"))
      (node (ref "U22") (pin "55") (pinfunction "VCCH_55") (pintype "power_in"))
      (node (ref "U22") (pin "57") (pinfunction "VCCL_57") (pintype "power_in"))
      (node (ref "U22") (pin "73") (pinfunction "VCCH_73") (pintype "power_in"))
      (node (ref "U22") (pin "84") (pinfunction "VCCL_84") (pintype "power_in"))
      (node (ref "U22") (pin "92") (pinfunction "VCCH_92") (pintype "power_in"))
      (node (ref "U22") (pin "94") (pinfunction "VCCL_94") (pintype "power_in"))
      (node (ref "U22") (pin "99") (pinfunction "VCCL_99") (pintype "power_in"))
      (node (ref "UC1") (pin "1") (pinfunction "VDD_1") (pintype "power_in"))
    )
    (net (code "112") (name "unconnected-(PCF-BVD1-Pad46)") (class "Default")
      (node (ref "PCF") (pin "46") (pinfunction "BVD1_46") (pintype "passive+no_connect"))
    )
    (net (code "113") (name "unconnected-(PCF-BVD2-Pad45)") (class "Default")
      (node (ref "PCF") (pin "45") (pinfunction "BVD2_45") (pintype "passive+no_connect"))
    )
    (net (code "114") (name "unconnected-(PCF-INPACK-Pad43)") (class "Default")
      (node (ref "PCF") (pin "43") (pinfunction "INPACK_43") (pintype "passive+no_connect"))
    )
    (net (code "115") (name "unconnected-(PCF-RDY{slash}BSY-Pad37)") (class "Default")
      (node (ref "PCF") (pin "37") (pinfunction "RDY/BSY_37") (pintype "passive+no_connect"))
    )
    (net (code "116") (name "unconnected-(PCF-VS1-Pad33)") (class "Default")
      (node (ref "PCF") (pin "33") (pinfunction "VS1_33") (pintype "passive+no_connect"))
    )
    (net (code "117") (name "unconnected-(PCF-VS2-Pad40)") (class "Default")
      (node (ref "PCF") (pin "40") (pinfunction "VS2_40") (pintype "passive+no_connect"))
    )
    (net (code "118") (name "unconnected-(PCF-WP-Pad24)") (class "Default")
      (node (ref "PCF") (pin "24") (pinfunction "WP_24") (pintype "passive+no_connect"))
    )
    (net (code "119") (name "unconnected-(U1H-CCLK_0-PadR17)") (class "Default")
      (node (ref "U1") (pin "R17") (pinfunction "CCLK_0_R17") (pintype "bidirectional+no_connect"))
    )
    (net (code "120") (name "unconnected-(U1H-DOUT_BUSY_0-PadY18)") (class "Default")
      (node (ref "U1") (pin "Y18") (pinfunction "DOUT_BUSY_0_Y18") (pintype "output+no_connect"))
    )
    (net (code "121") (name "unconnected-(U1H-D_IN_0-PadT16)") (class "Default")
      (node (ref "U1") (pin "T16") (pinfunction "D_IN_0_T16") (pintype "input+no_connect"))
    )
    (net (code "122") (name "unconnected-(U1H-PWRDWN_B_0-PadW21)") (class "Default")
      (node (ref "U1") (pin "W21") (pinfunction "PWRDWN_B_0_W21") (pintype "input+no_connect"))
    )
    (net (code "123") (name "unconnected-(U22-NC-Pad2)") (class "Default")
      (node (ref "U22") (pin "2") (pinfunction "NC_2") (pintype "passive+no_connect"))
    )
    (net (code "124") (name "unconnected-(U22-NC-Pad14)") (class "Default")
      (node (ref "U22") (pin "14") (pinfunction "NC_14") (pintype "passive+no_connect"))
    )
    (net (code "125") (name "unconnected-(U22-NC-Pad16)") (class "Default")
      (node (ref "U22") (pin "16") (pinfunction "NC_16") (pintype "passive+no_connect"))
    )
    (net (code "126") (name "unconnected-(U22-NC-Pad19)") (class "Default")
      (node (ref "U22") (pin "19") (pinfunction "NC_19") (pintype "passive+no_connect"))
    )
    (net (code "127") (name "unconnected-(U22-NC-Pad20)") (class "Default")
      (node (ref "U22") (pin "20") (pinfunction "NC_20") (pintype "passive+no_connect"))
    )
    (net (code "128") (name "unconnected-(U22-NC-Pad21)") (class "Default")
      (node (ref "U22") (pin "21") (pinfunction "NC_21") (pintype "passive+no_connect"))
    )
    (net (code "129") (name "unconnected-(U22-NC-Pad22)") (class "Default")
      (node (ref "U22") (pin "22") (pinfunction "NC_22") (pintype "passive+no_connect"))
    )
    (net (code "130") (name "unconnected-(U22-NC-Pad23)") (class "Default")
      (node (ref "U22") (pin "23") (pinfunction "NC_23") (pintype "passive+no_connect"))
    )
    (net (code "131") (name "unconnected-(U22-NC-Pad24)") (class "Default")
      (node (ref "U22") (pin "24") (pinfunction "NC_24") (pintype "passive+no_connect"))
    )
    (net (code "132") (name "unconnected-(U22-NC-Pad27)") (class "Default")
      (node (ref "U22") (pin "27") (pinfunction "NC_27") (pintype "passive+no_connect"))
    )
    (net (code "133") (name "unconnected-(U22-NC-Pad28)") (class "Default")
      (node (ref "U22") (pin "28") (pinfunction "NC_28") (pintype "passive+no_connect"))
    )
    (net (code "134") (name "unconnected-(U22-NC-Pad29)") (class "Default")
      (node (ref "U22") (pin "29") (pinfunction "NC_29") (pintype "passive+no_connect"))
    )
    (net (code "135") (name "unconnected-(U22-NC-Pad30)") (class "Default")
      (node (ref "U22") (pin "30") (pinfunction "NC_30") (pintype "passive+no_connect"))
    )
    (net (code "136") (name "unconnected-(U22-NC-Pad31)") (class "Default")
      (node (ref "U22") (pin "31") (pinfunction "NC_31") (pintype "passive+no_connect"))
    )
    (net (code "137") (name "unconnected-(U22-NC-Pad32)") (class "Default")
      (node (ref "U22") (pin "32") (pinfunction "NC_32") (pintype "passive+no_connect"))
    )
    (net (code "138") (name "unconnected-(U22-NC-Pad34)") (class "Default")
      (node (ref "U22") (pin "34") (pinfunction "NC_34") (pintype "passive+no_connect"))
    )
    (net (code "139") (name "unconnected-(U22-NC-Pad36)") (class "Default")
      (node (ref "U22") (pin "36") (pinfunction "NC_36") (pintype "passive+no_connect"))
    )
    (net (code "140") (name "unconnected-(U22-NC-Pad38)") (class "Default")
      (node (ref "U22") (pin "38") (pinfunction "NC_38") (pintype "passive+no_connect"))
    )
    (net (code "141") (name "unconnected-(U22-NC-Pad40)") (class "Default")
      (node (ref "U22") (pin "40") (pinfunction "NC_40") (pintype "passive+no_connect"))
    )
    (net (code "142") (name "unconnected-(U22-NC-Pad71)") (class "Default")
      (node (ref "U22") (pin "71") (pinfunction "NC_71") (pintype "passive+no_connect"))
    )
    (net (code "143") (name "unconnected-(U22-NC-Pad90)") (class "Default")
      (node (ref "U22") (pin "90") (pinfunction "NC_90") (pintype "passive+no_connect"))
    )
    (net (code "144") (name "unconnected-(U22-NC-Pad122)") (class "Default")
      (node (ref "U22") (pin "122") (pinfunction "NC_122") (pintype "passive+no_connect"))
    )
    (net (code "145") (name "unconnected-(U22-NC-Pad124)") (class "Default")
      (node (ref "U22") (pin "124") (pinfunction "NC_124") (pintype "passive+no_connect"))
    )
    (net (code "146") (name "unconnected-(U22-NC-Pad127)") (class "Default")
      (node (ref "U22") (pin "127") (pinfunction "NC_127") (pintype "passive+no_connect"))
    )
    (net (code "147") (name "unconnected-(U22-NC-Pad143)") (class "Default")
      (node (ref "U22") (pin "143") (pinfunction "NC_143") (pintype "passive+no_connect"))
    )
    (net (code "148") (name "unconnected-(U22-~{POR_TEST}-Pad74)") (class "Default")
      (node (ref "U22") (pin "74") (pinfunction "~{POR_TEST}_74") (pintype "output+no_connect"))
    )
    (net (code "149") (name "unconnected-(UC1-TLOW-Pad6)") (class "Default")
      (node (ref "UC1") (pin "6") (pinfunction "TLOW_6") (pintype "passive+no_connect"))
    )
  )
)
